# bltthBoard.net
KiCad netlist of a schematic drawn in EAGLE
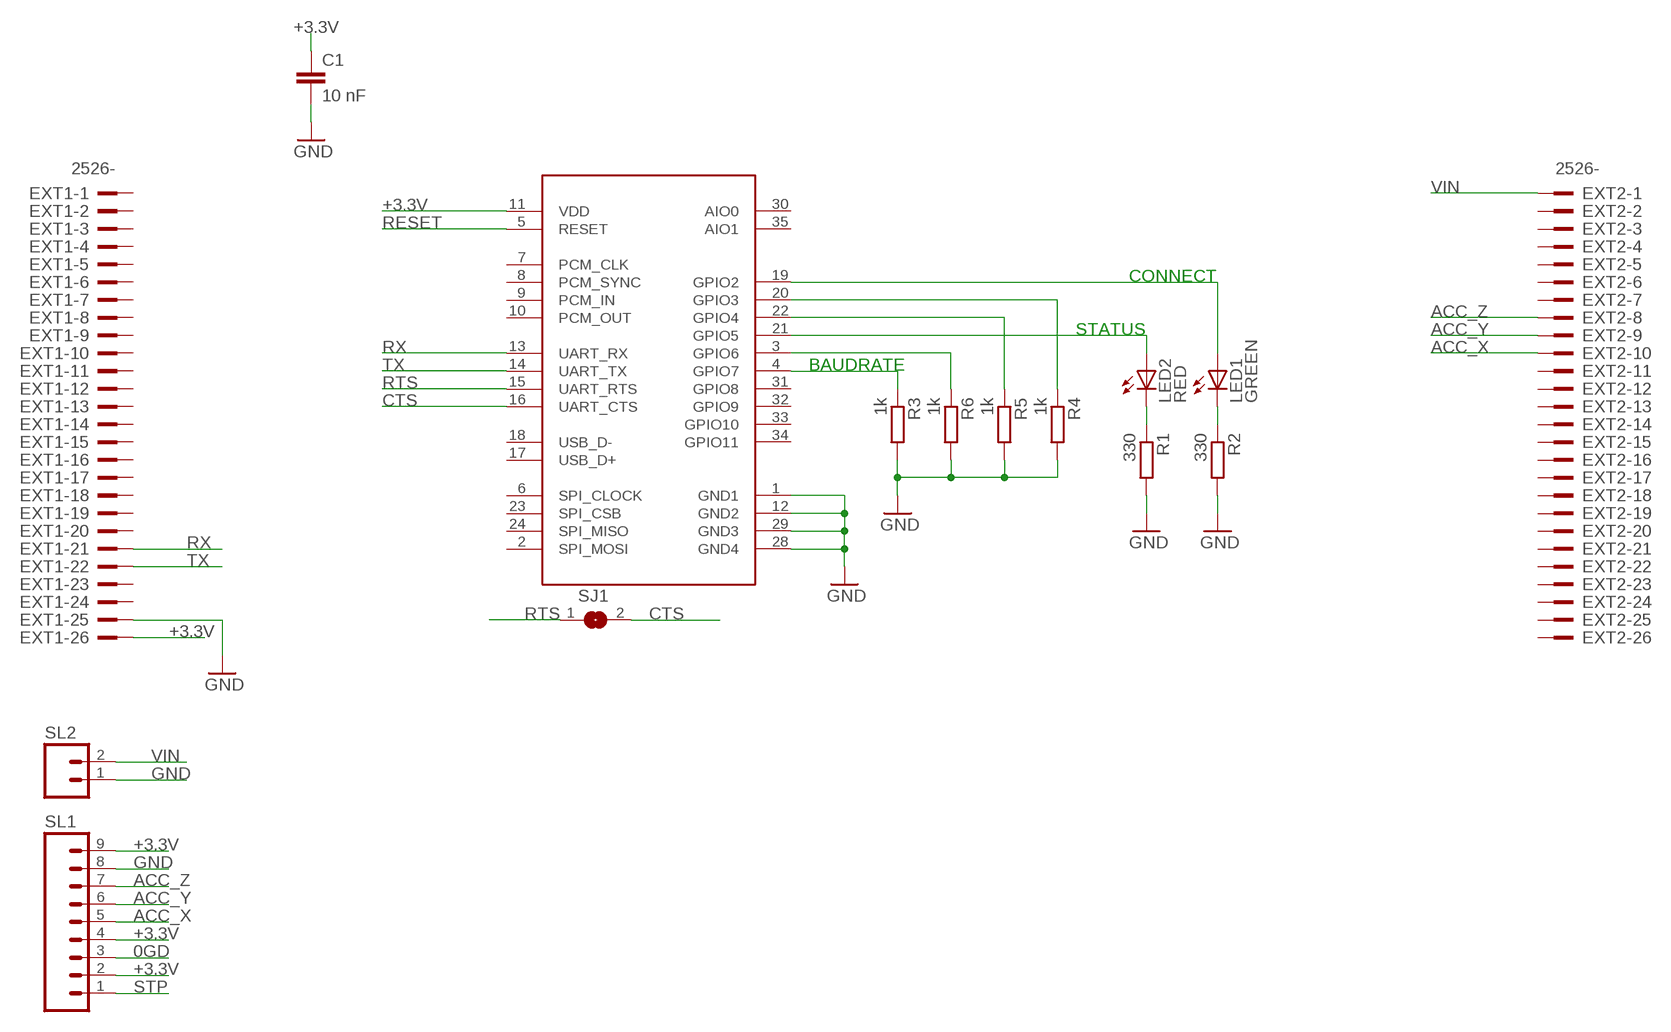
[diagram p0: schematic, sheet 1]

(export (version "E")
  (design (tool "Eeschema 10.0.6"))
  (components
    (comp (ref "C1")
      (value "10 nF")
      (footprint "eagle-import:C0402")
      (libsource (lib "eagle-import") (part "C-EUC0402"))
    )
    (comp (ref "EXT1")
      (value "2526-")
      (footprint "eagle-import:PAK100_2500-26")
      (libsource (lib "eagle-import") (part "2526-"))
    )
    (comp (ref "EXT2")
      (value "2526-")
      (footprint "eagle-import:PAK100_2500-26")
      (libsource (lib "eagle-import") (part "2526-"))
    )
    (comp (ref "LED1")
      (value "GREEN")
      (footprint "eagle-import:CHIP-LED0805")
      (libsource (lib "eagle-import") (part "LEDCHIP-LED0805"))
    )
    (comp (ref "LED2")
      (value "RED")
      (footprint "eagle-import:CHIP-LED0805")
      (libsource (lib "eagle-import") (part "LEDCHIP-LED0805"))
    )
    (comp (ref "R1")
      (value "330")
      (footprint "eagle-import:M0805")
      (libsource (lib "eagle-import") (part "R-EU_M0805"))
    )
    (comp (ref "R2")
      (value "330")
      (footprint "eagle-import:M0805")
      (libsource (lib "eagle-import") (part "R-EU_M0805"))
    )
    (comp (ref "R3")
      (value "1k")
      (footprint "eagle-import:M0805")
      (libsource (lib "eagle-import") (part "R-EU_M0805"))
    )
    (comp (ref "R4")
      (value "1k")
      (footprint "eagle-import:M0805")
      (libsource (lib "eagle-import") (part "R-EU_M0805"))
    )
    (comp (ref "R5")
      (value "1k")
      (footprint "eagle-import:M0805")
      (libsource (lib "eagle-import") (part "R-EU_M0805"))
    )
    (comp (ref "R6")
      (value "1k")
      (footprint "eagle-import:M0805")
      (libsource (lib "eagle-import") (part "R-EU_M0805"))
    )
    (comp (ref "SJ1") (value "SJ") (footprint "eagle-import:SJ") (libsource (lib "eagle-import") (part "SJ")))
    (comp (ref "SL1")
      (value "M09")
      (footprint "eagle-import:09P")
      (libsource (lib "eagle-import") (part "M09"))
    )
    (comp (ref "SL2")
      (value "M02")
      (footprint "eagle-import:02P")
      (libsource (lib "eagle-import") (part "M02"))
    )
    (comp (ref "U$1")
      (value "U1")
      (footprint "eagle-import:BLUETOOTH-RN42")
      (libsource (lib "eagle-import") (part "BLUETOOTH-RN42"))
    )
  )
  (nets
    (net (code "1") (name "/+3.3V") (class "Default")
      (node (ref "C1") (pin "1") (pinfunction "1_1") (pintype "passive"))
      (node (ref "EXT1") (pin "26") (pinfunction "KL_26") (pintype "passive"))
      (node (ref "SL1") (pin "2") (pinfunction "2_2") (pintype "passive"))
      (node (ref "SL1") (pin "4") (pinfunction "4_4") (pintype "passive"))
      (node (ref "SL1") (pin "9") (pinfunction "9_9") (pintype "passive"))
      (node (ref "U$1") (pin "11") (pinfunction "VDD_11") (pintype "power_in"))
    )
    (net (code "2") (name "/0GD") (class "Default")
      (node (ref "SL1") (pin "3") (pinfunction "3_3") (pintype "passive"))
    )
    (net (code "3") (name "/ACC_X") (class "Default")
      (node (ref "EXT2") (pin "10") (pinfunction "KL_10") (pintype "passive"))
      (node (ref "SL1") (pin "5") (pinfunction "5_5") (pintype "passive"))
    )
    (net (code "4") (name "/ACC_Y") (class "Default")
      (node (ref "EXT2") (pin "9") (pinfunction "KL_9") (pintype "passive"))
      (node (ref "SL1") (pin "6") (pinfunction "6_6") (pintype "passive"))
    )
    (net (code "5") (name "/ACC_Z") (class "Default")
      (node (ref "EXT2") (pin "8") (pinfunction "KL_8") (pintype "passive"))
      (node (ref "SL1") (pin "7") (pinfunction "7_7") (pintype "passive"))
    )
    (net (code "6") (name "/CTS") (class "Default")
      (node (ref "SJ1") (pin "2") (pinfunction "2_2") (pintype "passive"))
      (node (ref "U$1") (pin "16") (pinfunction "UART_CTS_16") (pintype "bidirectional"))
    )
    (net (code "7") (name "/RESET") (class "Default")
      (node (ref "U$1") (pin "5") (pinfunction "RESET_5") (pintype "bidirectional"))
    )
    (net (code "8") (name "/RTS") (class "Default")
      (node (ref "SJ1") (pin "1") (pinfunction "1_1") (pintype "passive"))
      (node (ref "U$1") (pin "15") (pinfunction "UART_RTS_15") (pintype "bidirectional"))
    )
    (net (code "9") (name "/RX") (class "Default")
      (node (ref "EXT1") (pin "21") (pinfunction "KL_21") (pintype "passive"))
      (node (ref "U$1") (pin "13") (pinfunction "UART_RX_13") (pintype "bidirectional"))
    )
    (net (code "10") (name "/STP") (class "Default")
      (node (ref "SL1") (pin "1") (pinfunction "1_1") (pintype "passive"))
    )
    (net (code "11") (name "/TX") (class "Default")
      (node (ref "EXT1") (pin "22") (pinfunction "KL_22") (pintype "passive"))
      (node (ref "U$1") (pin "14") (pinfunction "UART_TX_14") (pintype "bidirectional"))
    )
    (net (code "12") (name "/VIN") (class "Default")
      (node (ref "EXT2") (pin "1") (pinfunction "KL_1") (pintype "passive"))
      (node (ref "SL2") (pin "2") (pinfunction "2_2") (pintype "passive"))
    )
    (net (code "13") (name "GND") (class "Default")
      (node (ref "C1") (pin "2") (pinfunction "2_2") (pintype "passive"))
      (node (ref "EXT1") (pin "25") (pinfunction "KL_25") (pintype "passive"))
      (node (ref "R1") (pin "2") (pinfunction "2_2") (pintype "passive"))
      (node (ref "R2") (pin "2") (pinfunction "2_2") (pintype "passive"))
      (node (ref "R3") (pin "2") (pinfunction "2_2") (pintype "passive"))
      (node (ref "R4") (pin "2") (pinfunction "2_2") (pintype "passive"))
      (node (ref "R5") (pin "2") (pinfunction "2_2") (pintype "passive"))
      (node (ref "R6") (pin "2") (pinfunction "2_2") (pintype "passive"))
      (node (ref "SL1") (pin "8") (pinfunction "8_8") (pintype "passive"))
      (node (ref "SL2") (pin "1") (pinfunction "1_1") (pintype "passive"))
      (node (ref "U$1") (pin "1") (pinfunction "GND1_1") (pintype "power_in"))
      (node (ref "U$1") (pin "12") (pinfunction "GND2_12") (pintype "power_in"))
      (node (ref "U$1") (pin "28") (pinfunction "GND4_28") (pintype "power_in"))
      (node (ref "U$1") (pin "29") (pinfunction "GND3_29") (pintype "power_in"))
    )
    (net (code "14") (name "Net-(LED1-PadC)") (class "Default")
      (node (ref "LED1") (pin "C") (pinfunction "C_C") (pintype "passive"))
      (node (ref "R2") (pin "1") (pinfunction "1_1") (pintype "passive"))
    )
    (net (code "15") (name "Net-(LED2-PadC)") (class "Default")
      (node (ref "LED2") (pin "C") (pinfunction "C_C") (pintype "passive"))
      (node (ref "R1") (pin "1") (pinfunction "1_1") (pintype "passive"))
    )
    (net (code "16") (name "Net-(U$1-GPIO2)") (class "Default")
      (node (ref "LED1") (pin "A") (pinfunction "A_A") (pintype "passive"))
      (node (ref "U$1") (pin "19") (pinfunction "GPIO2_19") (pintype "bidirectional"))
    )
    (net (code "17") (name "Net-(U$1-GPIO3)") (class "Default")
      (node (ref "R4") (pin "1") (pinfunction "1_1") (pintype "passive"))
      (node (ref "U$1") (pin "20") (pinfunction "GPIO3_20") (pintype "bidirectional"))
    )
    (net (code "18") (name "Net-(U$1-GPIO4)") (class "Default")
      (node (ref "R5") (pin "1") (pinfunction "1_1") (pintype "passive"))
      (node (ref "U$1") (pin "22") (pinfunction "GPIO4_22") (pintype "bidirectional"))
    )
    (net (code "19") (name "Net-(U$1-GPIO5)") (class "Default")
      (node (ref "LED2") (pin "A") (pinfunction "A_A") (pintype "passive"))
      (node (ref "U$1") (pin "21") (pinfunction "GPIO5_21") (pintype "bidirectional"))
    )
    (net (code "20") (name "Net-(U$1-GPIO6)") (class "Default")
      (node (ref "R6") (pin "1") (pinfunction "1_1") (pintype "passive"))
      (node (ref "U$1") (pin "3") (pinfunction "GPIO6_3") (pintype "bidirectional"))
    )
    (net (code "21") (name "Net-(U$1-GPIO7)") (class "Default")
      (node (ref "R3") (pin "1") (pinfunction "1_1") (pintype "passive"))
      (node (ref "U$1") (pin "4") (pinfunction "GPIO7_4") (pintype "bidirectional"))
    )
    (net (code "22") (name "unconnected-(EXT1A-KL-Pad1)") (class "Default")
      (node (ref "EXT1") (pin "1") (pinfunction "KL_1") (pintype "passive"))
    )
    (net (code "23") (name "unconnected-(EXT1B-KL-Pad10)") (class "Default")
      (node (ref "EXT1") (pin "10") (pinfunction "KL_10") (pintype "passive"))
    )
    (net (code "24") (name "unconnected-(EXT1C-KL-Pad11)") (class "Default")
      (node (ref "EXT1") (pin "11") (pinfunction "KL_11") (pintype "passive"))
    )
    (net (code "25") (name "unconnected-(EXT1D-KL-Pad12)") (class "Default")
      (node (ref "EXT1") (pin "12") (pinfunction "KL_12") (pintype "passive"))
    )
    (net (code "26") (name "unconnected-(EXT1E-KL-Pad13)") (class "Default")
      (node (ref "EXT1") (pin "13") (pinfunction "KL_13") (pintype "passive"))
    )
    (net (code "27") (name "unconnected-(EXT1F-KL-Pad14)") (class "Default")
      (node (ref "EXT1") (pin "14") (pinfunction "KL_14") (pintype "passive"))
    )
    (net (code "28") (name "unconnected-(EXT1G-KL-Pad15)") (class "Default")
      (node (ref "EXT1") (pin "15") (pinfunction "KL_15") (pintype "passive"))
    )
    (net (code "29") (name "unconnected-(EXT1H-KL-Pad16)") (class "Default")
      (node (ref "EXT1") (pin "16") (pinfunction "KL_16") (pintype "passive"))
    )
    (net (code "30") (name "unconnected-(EXT1I-KL-Pad17)") (class "Default")
      (node (ref "EXT1") (pin "17") (pinfunction "KL_17") (pintype "passive"))
    )
    (net (code "31") (name "unconnected-(EXT1J-KL-Pad18)") (class "Default")
      (node (ref "EXT1") (pin "18") (pinfunction "KL_18") (pintype "passive"))
    )
    (net (code "32") (name "unconnected-(EXT1K-KL-Pad19)") (class "Default")
      (node (ref "EXT1") (pin "19") (pinfunction "KL_19") (pintype "passive"))
    )
    (net (code "33") (name "unconnected-(EXT1L-KL-Pad2)") (class "Default")
      (node (ref "EXT1") (pin "2") (pinfunction "KL_2") (pintype "passive"))
    )
    (net (code "34") (name "unconnected-(EXT1M-KL-Pad20)") (class "Default")
      (node (ref "EXT1") (pin "20") (pinfunction "KL_20") (pintype "passive"))
    )
    (net (code "35") (name "unconnected-(EXT1P-KL-Pad23)") (class "Default")
      (node (ref "EXT1") (pin "23") (pinfunction "KL_23") (pintype "passive"))
    )
    (net (code "36") (name "unconnected-(EXT1Q-KL-Pad24)") (class "Default")
      (node (ref "EXT1") (pin "24") (pinfunction "KL_24") (pintype "passive"))
    )
    (net (code "37") (name "unconnected-(EXT1T-KL-Pad3)") (class "Default")
      (node (ref "EXT1") (pin "3") (pinfunction "KL_3") (pintype "passive"))
    )
    (net (code "38") (name "unconnected-(EXT1U-KL-Pad4)") (class "Default")
      (node (ref "EXT1") (pin "4") (pinfunction "KL_4") (pintype "passive"))
    )
    (net (code "39") (name "unconnected-(EXT1V-KL-Pad5)") (class "Default")
      (node (ref "EXT1") (pin "5") (pinfunction "KL_5") (pintype "passive"))
    )
    (net (code "40") (name "unconnected-(EXT1W-KL-Pad6)") (class "Default")
      (node (ref "EXT1") (pin "6") (pinfunction "KL_6") (pintype "passive"))
    )
    (net (code "41") (name "unconnected-(EXT1X-KL-Pad7)") (class "Default")
      (node (ref "EXT1") (pin "7") (pinfunction "KL_7") (pintype "passive"))
    )
    (net (code "42") (name "unconnected-(EXT1Y-KL-Pad8)") (class "Default")
      (node (ref "EXT1") (pin "8") (pinfunction "KL_8") (pintype "passive"))
    )
    (net (code "43") (name "unconnected-(EXT1Z-KL-Pad9)") (class "Default")
      (node (ref "EXT1") (pin "9") (pinfunction "KL_9") (pintype "passive"))
    )
    (net (code "44") (name "unconnected-(EXT2C-KL-Pad11)") (class "Default")
      (node (ref "EXT2") (pin "11") (pinfunction "KL_11") (pintype "passive"))
    )
    (net (code "45") (name "unconnected-(EXT2D-KL-Pad12)") (class "Default")
      (node (ref "EXT2") (pin "12") (pinfunction "KL_12") (pintype "passive"))
    )
    (net (code "46") (name "unconnected-(EXT2E-KL-Pad13)") (class "Default")
      (node (ref "EXT2") (pin "13") (pinfunction "KL_13") (pintype "passive"))
    )
    (net (code "47") (name "unconnected-(EXT2F-KL-Pad14)") (class "Default")
      (node (ref "EXT2") (pin "14") (pinfunction "KL_14") (pintype "passive"))
    )
    (net (code "48") (name "unconnected-(EXT2G-KL-Pad15)") (class "Default")
      (node (ref "EXT2") (pin "15") (pinfunction "KL_15") (pintype "passive"))
    )
    (net (code "49") (name "unconnected-(EXT2H-KL-Pad16)") (class "Default")
      (node (ref "EXT2") (pin "16") (pinfunction "KL_16") (pintype "passive"))
    )
    (net (code "50") (name "unconnected-(EXT2I-KL-Pad17)") (class "Default")
      (node (ref "EXT2") (pin "17") (pinfunction "KL_17") (pintype "passive"))
    )
    (net (code "51") (name "unconnected-(EXT2J-KL-Pad18)") (class "Default")
      (node (ref "EXT2") (pin "18") (pinfunction "KL_18") (pintype "passive"))
    )
    (net (code "52") (name "unconnected-(EXT2K-KL-Pad19)") (class "Default")
      (node (ref "EXT2") (pin "19") (pinfunction "KL_19") (pintype "passive"))
    )
    (net (code "53") (name "unconnected-(EXT2L-KL-Pad2)") (class "Default")
      (node (ref "EXT2") (pin "2") (pinfunction "KL_2") (pintype "passive"))
    )
    (net (code "54") (name "unconnected-(EXT2M-KL-Pad20)") (class "Default")
      (node (ref "EXT2") (pin "20") (pinfunction "KL_20") (pintype "passive"))
    )
    (net (code "55") (name "unconnected-(EXT2N-KL-Pad21)") (class "Default")
      (node (ref "EXT2") (pin "21") (pinfunction "KL_21") (pintype "passive"))
    )
    (net (code "56") (name "unconnected-(EXT2O-KL-Pad22)") (class "Default")
      (node (ref "EXT2") (pin "22") (pinfunction "KL_22") (pintype "passive"))
    )
    (net (code "57") (name "unconnected-(EXT2P-KL-Pad23)") (class "Default")
      (node (ref "EXT2") (pin "23") (pinfunction "KL_23") (pintype "passive"))
    )
    (net (code "58") (name "unconnected-(EXT2Q-KL-Pad24)") (class "Default")
      (node (ref "EXT2") (pin "24") (pinfunction "KL_24") (pintype "passive"))
    )
    (net (code "59") (name "unconnected-(EXT2R-KL-Pad25)") (class "Default")
      (node (ref "EXT2") (pin "25") (pinfunction "KL_25") (pintype "passive"))
    )
    (net (code "60") (name "unconnected-(EXT2S-KL-Pad26)") (class "Default")
      (node (ref "EXT2") (pin "26") (pinfunction "KL_26") (pintype "passive"))
    )
    (net (code "61") (name "unconnected-(EXT2T-KL-Pad3)") (class "Default")
      (node (ref "EXT2") (pin "3") (pinfunction "KL_3") (pintype "passive"))
    )
    (net (code "62") (name "unconnected-(EXT2U-KL-Pad4)") (class "Default")
      (node (ref "EXT2") (pin "4") (pinfunction "KL_4") (pintype "passive"))
    )
    (net (code "63") (name "unconnected-(EXT2V-KL-Pad5)") (class "Default")
      (node (ref "EXT2") (pin "5") (pinfunction "KL_5") (pintype "passive"))
    )
    (net (code "64") (name "unconnected-(EXT2W-KL-Pad6)") (class "Default")
      (node (ref "EXT2") (pin "6") (pinfunction "KL_6") (pintype "passive"))
    )
    (net (code "65") (name "unconnected-(EXT2X-KL-Pad7)") (class "Default")
      (node (ref "EXT2") (pin "7") (pinfunction "KL_7") (pintype "passive"))
    )
    (net (code "66") (name "unconnected-(U$1-AIO0-Pad30)") (class "Default")
      (node (ref "U$1") (pin "30") (pinfunction "AIO0_30") (pintype "bidirectional"))
    )
    (net (code "67") (name "unconnected-(U$1-AIO1-Pad35)") (class "Default")
      (node (ref "U$1") (pin "35") (pinfunction "AIO1_35") (pintype "bidirectional"))
    )
    (net (code "68") (name "unconnected-(U$1-GPIO8-Pad31)") (class "Default")
      (node (ref "U$1") (pin "31") (pinfunction "GPIO8_31") (pintype "bidirectional"))
    )
    (net (code "69") (name "unconnected-(U$1-GPIO9-Pad32)") (class "Default")
      (node (ref "U$1") (pin "32") (pinfunction "GPIO9_32") (pintype "bidirectional"))
    )
    (net (code "70") (name "unconnected-(U$1-GPIO10-Pad33)") (class "Default")
      (node (ref "U$1") (pin "33") (pinfunction "GPIO10_33") (pintype "bidirectional"))
    )
    (net (code "71") (name "unconnected-(U$1-GPIO11-Pad34)") (class "Default")
      (node (ref "U$1") (pin "34") (pinfunction "GPIO11_34") (pintype "bidirectional"))
    )
    (net (code "72") (name "unconnected-(U$1-PCM_CLK-Pad7)") (class "Default")
      (node (ref "U$1") (pin "7") (pinfunction "PCM_CLK_7") (pintype "bidirectional"))
    )
    (net (code "73") (name "unconnected-(U$1-PCM_IN-Pad9)") (class "Default")
      (node (ref "U$1") (pin "9") (pinfunction "PCM_IN_9") (pintype "bidirectional"))
    )
    (net (code "74") (name "unconnected-(U$1-PCM_OUT-Pad10)") (class "Default")
      (node (ref "U$1") (pin "10") (pinfunction "PCM_OUT_10") (pintype "bidirectional"))
    )
    (net (code "75") (name "unconnected-(U$1-PCM_SYNC-Pad8)") (class "Default")
      (node (ref "U$1") (pin "8") (pinfunction "PCM_SYNC_8") (pintype "bidirectional"))
    )
    (net (code "76") (name "unconnected-(U$1-SPI_CLOCK-Pad6)") (class "Default")
      (node (ref "U$1") (pin "6") (pinfunction "SPI_CLOCK_6") (pintype "bidirectional"))
    )
    (net (code "77") (name "unconnected-(U$1-SPI_CSB-Pad23)") (class "Default")
      (node (ref "U$1") (pin "23") (pinfunction "SPI_CSB_23") (pintype "bidirectional"))
    )
    (net (code "78") (name "unconnected-(U$1-SPI_MISO-Pad24)") (class "Default")
      (node (ref "U$1") (pin "24") (pinfunction "SPI_MISO_24") (pintype "bidirectional"))
    )
    (net (code "79") (name "unconnected-(U$1-SPI_MOSI-Pad2)") (class "Default")
      (node (ref "U$1") (pin "2") (pinfunction "SPI_MOSI_2") (pintype "bidirectional"))
    )
    (net (code "80") (name "unconnected-(U$1-USB_D+-Pad17)") (class "Default")
      (node (ref "U$1") (pin "17") (pinfunction "USB_D+_17") (pintype "bidirectional"))
    )
    (net (code "81") (name "unconnected-(U$1-USB_D--Pad18)") (class "Default")
      (node (ref "U$1") (pin "18") (pinfunction "USB_D-_18") (pintype "bidirectional"))
    )
  )
)
